# LB-w4-DOUBLE_AND_v02_rev2.net
KiCad netlist of a schematic drawn in EAGLE
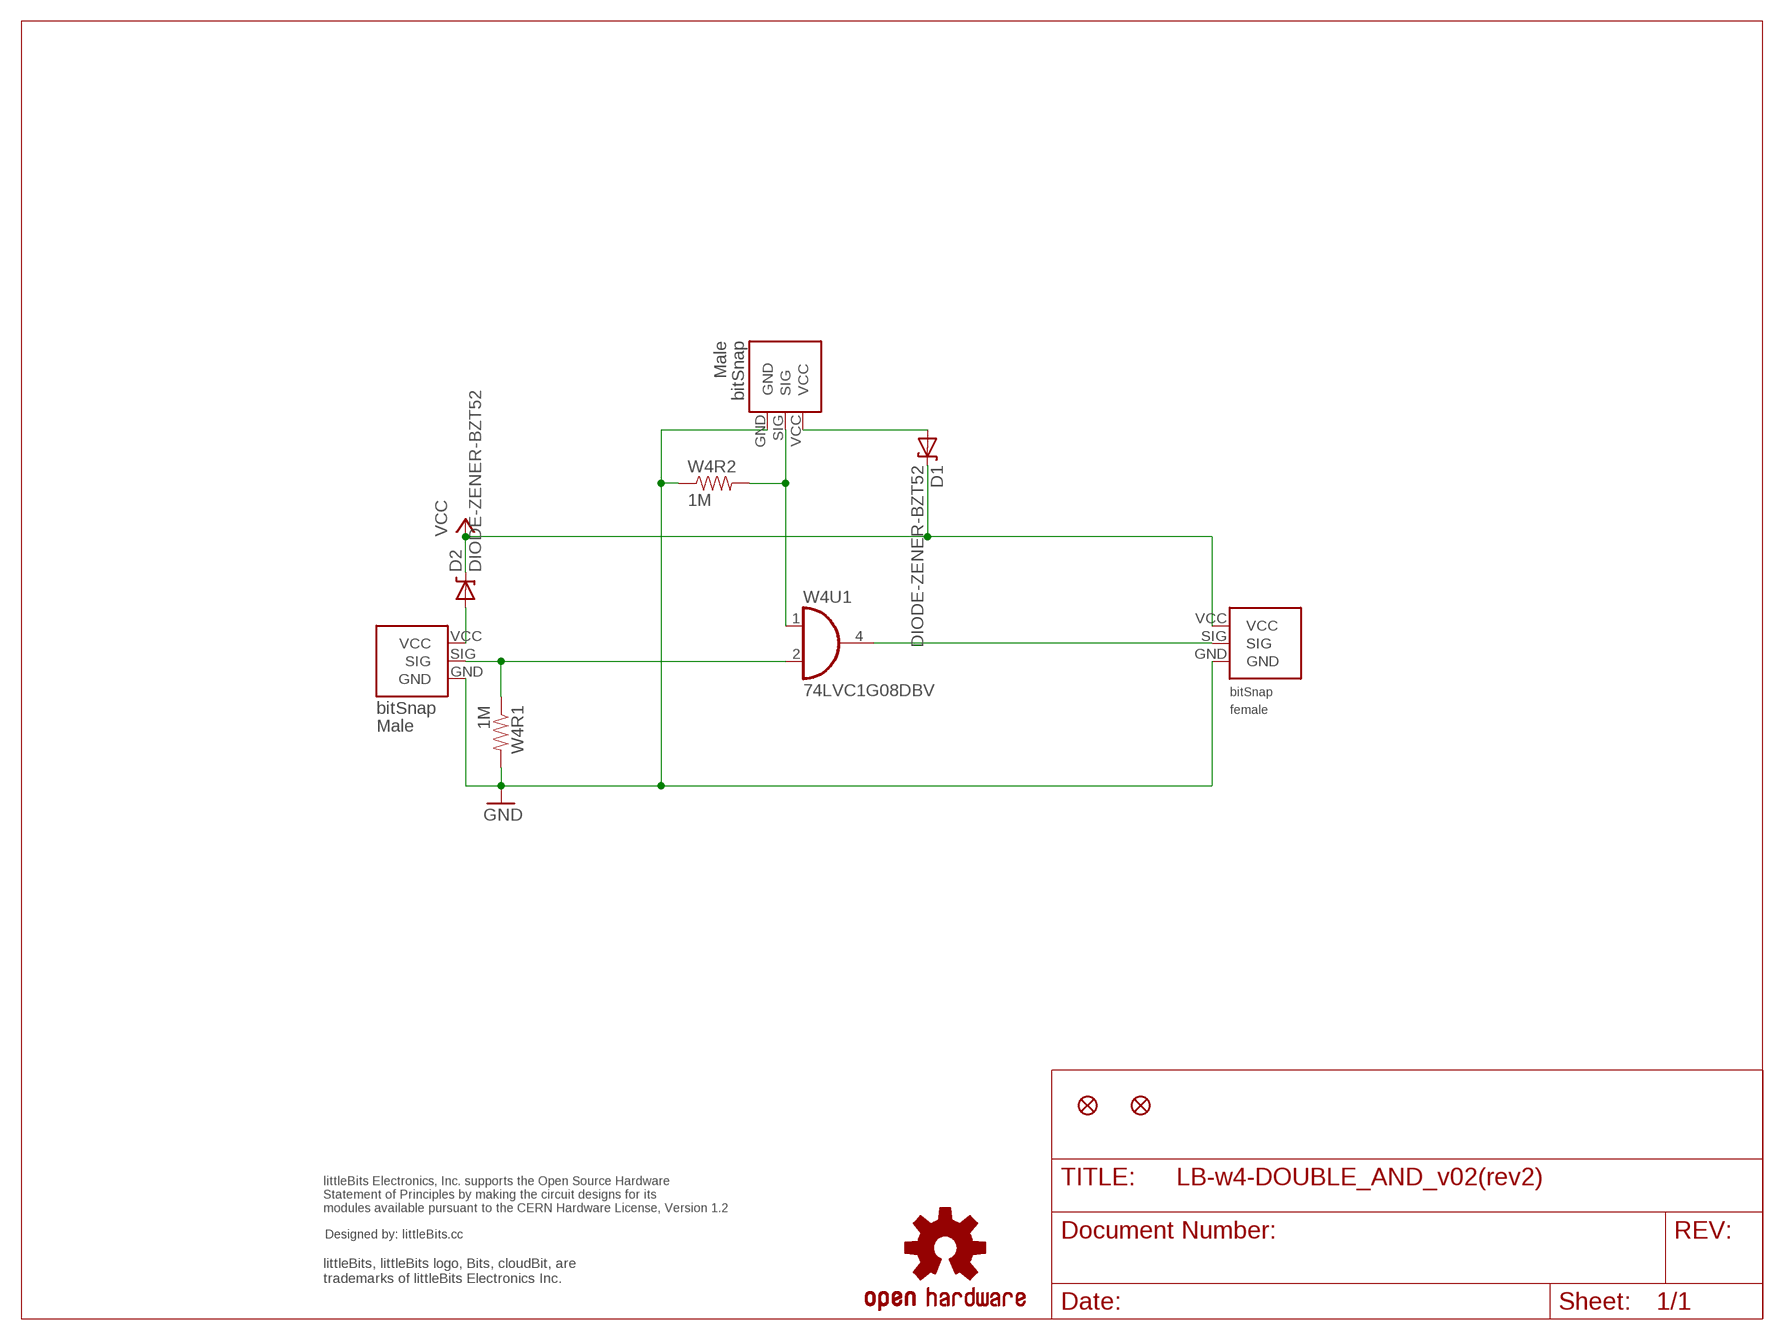
[diagram p0: schematic, sheet 1]

(export (version "E")
  (design (tool "Eeschema 10.0.6"))
  (components
    (comp (ref "D1")
      (value "DIODE-ZENER-BZT52")
      (footprint "eagle-import:SOD-323")
      (libsource (lib "eagle-import") (part "DIODE-ZENER-BZT52"))
    )
    (comp (ref "D2")
      (value "DIODE-ZENER-BZT52")
      (footprint "eagle-import:SOD-323")
      (libsource (lib "eagle-import") (part "DIODE-ZENER-BZT52"))
    )
    (comp (ref "U$1")
      (value "OSHW-LOGOL")
      (footprint "eagle-import:OSHW-LOGO-L")
      (libsource (lib "eagle-import") (part "OSHW-LOGOL"))
    )
    (comp (ref "U$2")
      (value "OSHWCREDIT")
      (footprint "eagle-import:OSHWCREDIT")
      (libsource (lib "eagle-import") (part "OSHWCREDIT"))
    )
    (comp (ref "W4BSF")
      (value "BITSNAP_FEMALE")
      (footprint "eagle-import:BITSNAP_FEMALE")
      (libsource (lib "eagle-import") (part "BITSNAP_FEMALE"))
    )
    (comp (ref "W4BSM1")
      (value "BITSNAP_MALE")
      (footprint "eagle-import:BITSNAP_MALE")
      (libsource (lib "eagle-import") (part "BITSNAP_MALE"))
    )
    (comp (ref "W4BSM2")
      (value "BITSNAP_MALE")
      (footprint "eagle-import:BITSNAP_MALE")
      (libsource (lib "eagle-import") (part "BITSNAP_MALE"))
    )
    (comp (ref "W4FD1")
      (value "FIDUCIAL1X2")
      (footprint "eagle-import:FIDUCIAL-1X2")
      (libsource (lib "eagle-import") (part "FIDUCIAL1X2"))
    )
    (comp (ref "W4FD2")
      (value "FIDUCIAL1X2")
      (footprint "eagle-import:FIDUCIAL-1X2")
      (libsource (lib "eagle-import") (part "FIDUCIAL1X2"))
    )
    (comp (ref "W4R1")
      (value "1M")
      (footprint "eagle-import:0603-RES")
      (libsource (lib "eagle-import") (part "RESISTOR0603-RES"))
    )
    (comp (ref "W4R2")
      (value "1M")
      (footprint "eagle-import:0603-RES")
      (libsource (lib "eagle-import") (part "RESISTOR0603-RES"))
    )
    (comp (ref "W4U1")
      (value "74LVC1G08DBV")
      (footprint "eagle-import:SOT23-5")
      (libsource (lib "eagle-import") (part "741G08DBVLVC"))
    )
  )
  (nets
    (net (code "1") (name "GND") (class "Default")
      (node (ref "W4BSF") (pin "GND") (pinfunction "GND_GND") (pintype "bidirectional"))
      (node (ref "W4BSM1") (pin "GND") (pinfunction "GND_GND") (pintype "bidirectional"))
      (node (ref "W4BSM2") (pin "GND") (pinfunction "GND_GND") (pintype "bidirectional"))
      (node (ref "W4R1") (pin "2") (pinfunction "2_2") (pintype "passive"))
      (node (ref "W4R2") (pin "1") (pinfunction "1_1") (pintype "passive"))
    )
    (net (code "2") (name "Net-(D1-A)") (class "Default")
      (node (ref "D1") (pin "2") (pinfunction "A_2") (pintype "passive"))
      (node (ref "W4BSM2") (pin "VCC") (pinfunction "VCC_VCC") (pintype "bidirectional"))
    )
    (net (code "3") (name "Net-(D2-A)") (class "Default")
      (node (ref "D2") (pin "2") (pinfunction "A_2") (pintype "passive"))
      (node (ref "W4BSM1") (pin "VCC") (pinfunction "VCC_VCC") (pintype "bidirectional"))
    )
    (net (code "4") (name "Net-(W4U1A-I0)") (class "Default")
      (node (ref "W4BSM2") (pin "SIG") (pinfunction "SIG_SIG") (pintype "bidirectional"))
      (node (ref "W4R2") (pin "2") (pinfunction "2_2") (pintype "passive"))
      (node (ref "W4U1") (pin "1") (pinfunction "I0_1") (pintype "input"))
    )
    (net (code "5") (name "Net-(W4U1A-I1)") (class "Default")
      (node (ref "W4BSM1") (pin "SIG") (pinfunction "SIG_SIG") (pintype "bidirectional"))
      (node (ref "W4R1") (pin "1") (pinfunction "1_1") (pintype "passive"))
      (node (ref "W4U1") (pin "2") (pinfunction "I1_2") (pintype "input"))
    )
    (net (code "6") (name "Net-(W4U1A-O)") (class "Default")
      (node (ref "W4BSF") (pin "SIG") (pinfunction "SIG_SIG") (pintype "bidirectional"))
      (node (ref "W4U1") (pin "4") (pinfunction "O_4") (pintype "output"))
    )
    (net (code "7") (name "VCC") (class "Default")
      (node (ref "D1") (pin "1") (pinfunction "C_1") (pintype "passive"))
      (node (ref "D2") (pin "1") (pinfunction "C_1") (pintype "passive"))
      (node (ref "W4BSF") (pin "VCC") (pinfunction "VCC_VCC") (pintype "bidirectional"))
    )
  )
)
